# design.net
KiCad netlist of a schematic drawn in Altium Designer
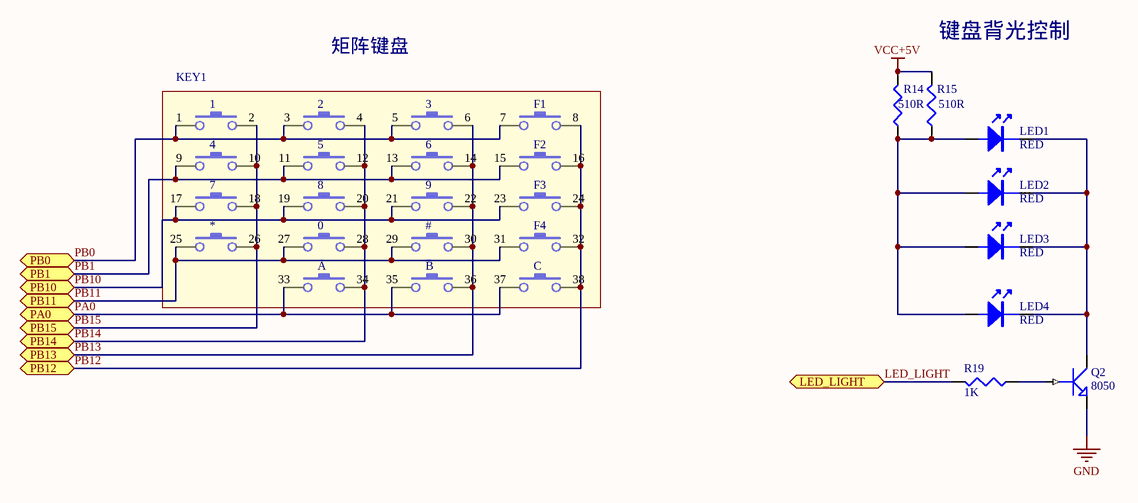
[diagram p0: 键盘.SchDoc]

(export (version "E")
  (design (tool "Eeschema 10.0.6"))
  (components
    (comp (ref "KEY1")
      (value "SW-17")
      (footprint "KEY-17")
      (description "终端操作按键")
      (libsource (lib "INSPUR_SCH") (part "SW-17"))
    )
    (comp (ref "LED1")
      (value "RED")
      (footprint "LED-0603")
      (description "LED贴片发光二极管0603封装")
      (libsource (lib "INSPUR_PCB") (part "LED-0603"))
    )
    (comp (ref "LED2")
      (value "RED")
      (footprint "LED-0603")
      (description "LED贴片发光二极管0603封装")
      (libsource (lib "INSPUR_PCB") (part "LED-0603"))
    )
    (comp (ref "LED3")
      (value "RED")
      (footprint "LED-0603")
      (description "LED贴片发光二极管0603封装")
      (libsource (lib "INSPUR_PCB") (part "LED-0603"))
    )
    (comp (ref "LED4")
      (value "RED")
      (footprint "LED-0603")
      (description "LED贴片发光二极管0603封装")
      (libsource (lib "INSPUR_PCB") (part "LED-0603"))
    )
    (comp (ref "Q2")
      (value "8050")
      (footprint "SOT-23")
      (description "8050 NPN型三极管")
      (libsource (lib "INSPUR_PCB") (part "8050"))
    )
    (comp (ref "R14")
      (value "510R")
      (footprint "0603")
      (description "陶瓷贴片电阻0603封装")
      (libsource (lib "INSPUR_PCB") (part "RES-0603"))
    )
    (comp (ref "R15")
      (value "510R")
      (footprint "0603")
      (description "陶瓷贴片电阻0603封装")
      (libsource (lib "INSPUR_PCB") (part "RES-0603"))
    )
    (comp (ref "R19")
      (value "1K")
      (footprint "0603")
      (description "陶瓷贴片电阻0603封装")
      (libsource (lib "INSPUR_PCB") (part "RES-0603"))
    )
  )
  (nets
    (net (code "1") (name "/LED_LIGHT") (class "Default")
      (node (ref "R19") (pin "2") (pinfunction "2_2") (pintype "passive"))
    )
    (net (code "2") (name "/PA0") (class "Default")
      (node (ref "KEY1") (pin "33") (pinfunction "33_33") (pintype "passive"))
      (node (ref "KEY1") (pin "35") (pinfunction "35_35") (pintype "passive"))
      (node (ref "KEY1") (pin "37") (pinfunction "37_37") (pintype "passive"))
    )
    (net (code "3") (name "/PB0") (class "Default")
      (node (ref "KEY1") (pin "1") (pintype "passive"))
      (node (ref "KEY1") (pin "3") (pinfunction "3_3") (pintype "passive"))
      (node (ref "KEY1") (pin "5") (pinfunction "5_5") (pintype "passive"))
      (node (ref "KEY1") (pin "7") (pinfunction "7_7") (pintype "passive"))
    )
    (net (code "4") (name "/PB1") (class "Default")
      (node (ref "KEY1") (pin "11") (pinfunction "11_11") (pintype "passive"))
      (node (ref "KEY1") (pin "13") (pinfunction "13_13") (pintype "passive"))
      (node (ref "KEY1") (pin "15") (pinfunction "15_15") (pintype "passive"))
      (node (ref "KEY1") (pin "9") (pinfunction "9_9") (pintype "passive"))
    )
    (net (code "5") (name "/PB10") (class "Default")
      (node (ref "KEY1") (pin "17") (pinfunction "17_17") (pintype "passive"))
      (node (ref "KEY1") (pin "19") (pinfunction "19_19") (pintype "passive"))
      (node (ref "KEY1") (pin "21") (pinfunction "21_21") (pintype "passive"))
      (node (ref "KEY1") (pin "23") (pinfunction "23_23") (pintype "passive"))
    )
    (net (code "6") (name "/PB11") (class "Default")
      (node (ref "KEY1") (pin "25") (pinfunction "25_25") (pintype "passive"))
      (node (ref "KEY1") (pin "27") (pinfunction "27_27") (pintype "passive"))
      (node (ref "KEY1") (pin "29") (pinfunction "29_29") (pintype "passive"))
      (node (ref "KEY1") (pin "31") (pinfunction "31_31") (pintype "passive"))
    )
    (net (code "7") (name "/PB12") (class "Default")
      (node (ref "KEY1") (pin "16") (pinfunction "16_16") (pintype "passive"))
      (node (ref "KEY1") (pin "24") (pinfunction "24_24") (pintype "passive"))
      (node (ref "KEY1") (pin "32") (pinfunction "32_32") (pintype "passive"))
      (node (ref "KEY1") (pin "38") (pinfunction "38_38") (pintype "passive"))
      (node (ref "KEY1") (pin "8") (pinfunction "8_8") (pintype "passive"))
    )
    (net (code "8") (name "/PB13") (class "Default")
      (node (ref "KEY1") (pin "14") (pinfunction "14_14") (pintype "passive"))
      (node (ref "KEY1") (pin "22") (pinfunction "22_22") (pintype "passive"))
      (node (ref "KEY1") (pin "30") (pinfunction "30_30") (pintype "passive"))
      (node (ref "KEY1") (pin "36") (pinfunction "36_36") (pintype "passive"))
      (node (ref "KEY1") (pin "6") (pinfunction "6_6") (pintype "passive"))
    )
    (net (code "9") (name "/PB14") (class "Default")
      (node (ref "KEY1") (pin "12") (pinfunction "12_12") (pintype "passive"))
      (node (ref "KEY1") (pin "20") (pinfunction "20_20") (pintype "passive"))
      (node (ref "KEY1") (pin "28") (pinfunction "28_28") (pintype "passive"))
      (node (ref "KEY1") (pin "34") (pinfunction "34_34") (pintype "passive"))
      (node (ref "KEY1") (pin "4") (pinfunction "4_4") (pintype "passive"))
    )
    (net (code "10") (name "/PB15") (class "Default")
      (node (ref "KEY1") (pin "10") (pinfunction "10_10") (pintype "passive"))
      (node (ref "KEY1") (pin "18") (pinfunction "18_18") (pintype "passive"))
      (node (ref "KEY1") (pin "2") (pinfunction "10_2") (pintype "passive"))
      (node (ref "KEY1") (pin "26") (pinfunction "26_26") (pintype "passive"))
    )
    (net (code "11") (name "GND") (class "Default")
      (node (ref "Q2") (pin "2") (pinfunction "E_2") (pintype "passive"))
    )
    (net (code "12") (name "Net-(LED1-Pad1)") (class "Default")
      (node (ref "LED1") (pin "1") (pinfunction "1_1") (pintype "passive"))
      (node (ref "LED2") (pin "1") (pinfunction "1_1") (pintype "passive"))
      (node (ref "LED3") (pin "1") (pinfunction "1_1") (pintype "passive"))
      (node (ref "LED4") (pin "1") (pinfunction "1_1") (pintype "passive"))
      (node (ref "R14") (pin "1") (pinfunction "1_1") (pintype "passive"))
      (node (ref "R15") (pin "1") (pinfunction "1_1") (pintype "passive"))
    )
    (net (code "13") (name "Net-(Q2-B)") (class "Default")
      (node (ref "Q2") (pin "1") (pinfunction "B_1") (pintype "input"))
      (node (ref "R19") (pin "1") (pinfunction "1_1") (pintype "passive"))
    )
    (net (code "14") (name "Net-(Q2-C)") (class "Default")
      (node (ref "LED1") (pin "2") (pinfunction "2_2") (pintype "passive"))
      (node (ref "LED2") (pin "2") (pinfunction "2_2") (pintype "passive"))
      (node (ref "LED3") (pin "2") (pinfunction "2_2") (pintype "passive"))
      (node (ref "LED4") (pin "2") (pinfunction "2_2") (pintype "passive"))
      (node (ref "Q2") (pin "3") (pinfunction "C_3") (pintype "passive"))
    )
    (net (code "15") (name "VCC+5V") (class "Default")
      (node (ref "R14") (pin "2") (pinfunction "2_2") (pintype "passive"))
      (node (ref "R15") (pin "2") (pinfunction "2_2") (pintype "passive"))
    )
  )
)
